# fpv-diversity.net
KiCad netlist of a schematic drawn in EAGLE
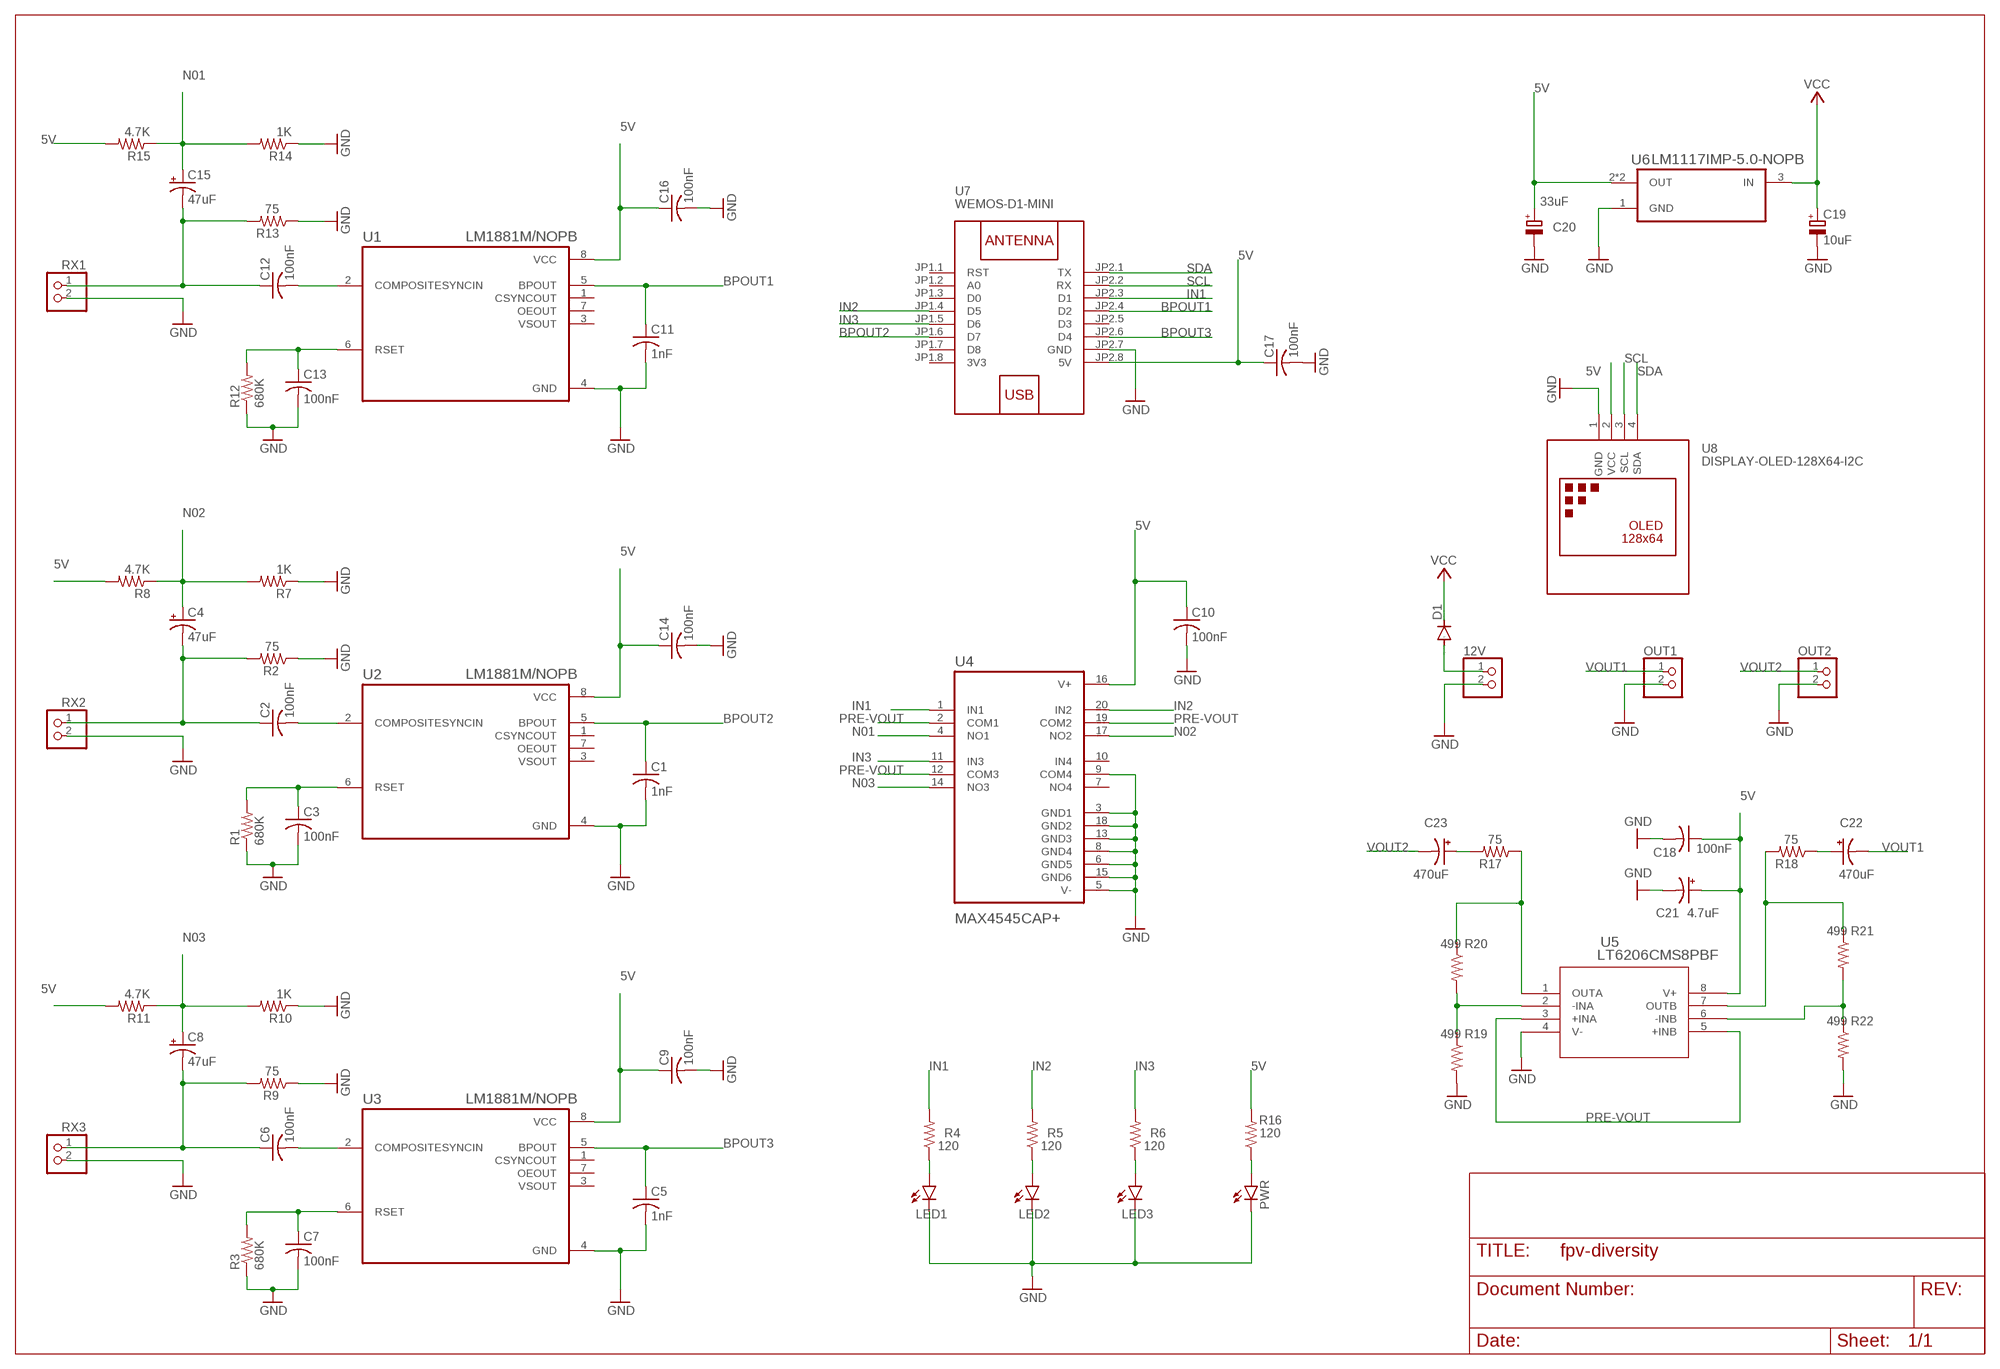
[diagram p0: schematic, sheet 1]

(export (version "E")
  (design (tool "Eeschema 10.0.6"))
  (components
    (comp (ref "12V")
      (value "PINHD-1X2")
      (footprint "eagle-import:1X02")
      (libsource (lib "eagle-import") (part "PINHD-1X2"))
    )
    (comp (ref "C1")
      (value "1nF")
      (footprint "eagle-import:C0603")
      (libsource (lib "eagle-import") (part "C-USC0603"))
    )
    (comp (ref "C2")
      (value "100nF")
      (footprint "eagle-import:C0805")
      (libsource (lib "eagle-import") (part "C-USC0805"))
    )
    (comp (ref "C3")
      (value "100nF")
      (footprint "eagle-import:C0805")
      (libsource (lib "eagle-import") (part "C-USC0805"))
    )
    (comp (ref "C4")
      (value "47uF")
      (footprint "eagle-import:CT3216")
      (libsource (lib "eagle-import") (part "CPOL-USCT3216"))
    )
    (comp (ref "C5")
      (value "1nF")
      (footprint "eagle-import:C0603")
      (libsource (lib "eagle-import") (part "C-USC0603"))
    )
    (comp (ref "C6")
      (value "100nF")
      (footprint "eagle-import:C0805")
      (libsource (lib "eagle-import") (part "C-USC0805"))
    )
    (comp (ref "C7")
      (value "100nF")
      (footprint "eagle-import:C0805")
      (libsource (lib "eagle-import") (part "C-USC0805"))
    )
    (comp (ref "C8")
      (value "47uF")
      (footprint "eagle-import:CT3216")
      (libsource (lib "eagle-import") (part "CPOL-USCT3216"))
    )
    (comp (ref "C9")
      (value "100nF")
      (footprint "eagle-import:C0805")
      (libsource (lib "eagle-import") (part "C-USC0805"))
    )
    (comp (ref "C10")
      (value "100nF")
      (footprint "eagle-import:C0805")
      (libsource (lib "eagle-import") (part "C-USC0805"))
    )
    (comp (ref "C11")
      (value "1nF")
      (footprint "eagle-import:C0603")
      (libsource (lib "eagle-import") (part "C-USC0603"))
    )
    (comp (ref "C12")
      (value "100nF")
      (footprint "eagle-import:C0805")
      (libsource (lib "eagle-import") (part "C-USC0805"))
    )
    (comp (ref "C13")
      (value "100nF")
      (footprint "eagle-import:C0805")
      (libsource (lib "eagle-import") (part "C-USC0805"))
    )
    (comp (ref "C14")
      (value "100nF")
      (footprint "eagle-import:C0805")
      (libsource (lib "eagle-import") (part "C-USC0805"))
    )
    (comp (ref "C15")
      (value "47uF")
      (footprint "eagle-import:CT3216")
      (libsource (lib "eagle-import") (part "CPOL-USCT3216"))
    )
    (comp (ref "C16")
      (value "100nF")
      (footprint "eagle-import:C0805")
      (libsource (lib "eagle-import") (part "C-USC0805"))
    )
    (comp (ref "C17")
      (value "100nF")
      (footprint "eagle-import:C0805")
      (libsource (lib "eagle-import") (part "C-USC0805"))
    )
    (comp (ref "C18")
      (value "100nF")
      (footprint "eagle-import:C0805")
      (libsource (lib "eagle-import") (part "C-USC0805"))
    )
    (comp (ref "C19")
      (value "10uF")
      (footprint "eagle-import:D_7343-31W")
      (libsource (lib "eagle-import") (part "CPOL-EUD/7343-31W"))
    )
    (comp (ref "C20")
      (value "33uF")
      (footprint "eagle-import:D_7343-31W")
      (libsource (lib "eagle-import") (part "CPOL-EUD/7343-31W"))
    )
    (comp (ref "C21")
      (value "4.7uF")
      (footprint "eagle-import:CT3528")
      (libsource (lib "eagle-import") (part "CPOL-USCT3528"))
    )
    (comp (ref "C22")
      (value "470uF")
      (footprint "eagle-import:UD-6,3X7,7_NICHICON")
      (libsource (lib "eagle-import") (part "CPOL-USUD-6,3X7,7"))
    )
    (comp (ref "C23")
      (value "470uF")
      (footprint "eagle-import:UD-6,3X7,7_NICHICON")
      (libsource (lib "eagle-import") (part "CPOL-USUD-6,3X7,7"))
    )
    (comp (ref "D1")
      (value "DIODE-DO-214AC")
      (footprint "eagle-import:DO-214AC")
      (libsource (lib "eagle-import") (part "DIODE-DO-214AC"))
    )
    (comp (ref "LED1")
      (value "LEDCHIPLED_0603")
      (footprint "eagle-import:CHIPLED_0603")
      (libsource (lib "eagle-import") (part "LEDCHIPLED_0603"))
    )
    (comp (ref "LED2")
      (value "LEDCHIPLED_0603")
      (footprint "eagle-import:CHIPLED_0603")
      (libsource (lib "eagle-import") (part "LEDCHIPLED_0603"))
    )
    (comp (ref "LED3")
      (value "LEDCHIPLED_0603")
      (footprint "eagle-import:CHIPLED_0603")
      (libsource (lib "eagle-import") (part "LEDCHIPLED_0603"))
    )
    (comp (ref "OUT1")
      (value "PINHD-1X2")
      (footprint "eagle-import:1X02")
      (libsource (lib "eagle-import") (part "PINHD-1X2"))
    )
    (comp (ref "OUT2")
      (value "PINHD-1X2")
      (footprint "eagle-import:1X02")
      (libsource (lib "eagle-import") (part "PINHD-1X2"))
    )
    (comp (ref "PWR")
      (value "LEDCHIPLED_0603")
      (footprint "eagle-import:CHIPLED_0603")
      (libsource (lib "eagle-import") (part "LEDCHIPLED_0603"))
    )
    (comp (ref "R1")
      (value "680K")
      (footprint "eagle-import:R0805")
      (libsource (lib "eagle-import") (part "R-US_R0805"))
    )
    (comp (ref "R2")
      (value "75")
      (footprint "eagle-import:R0805")
      (libsource (lib "eagle-import") (part "R-US_R0805"))
    )
    (comp (ref "R3")
      (value "680K")
      (footprint "eagle-import:R0805")
      (libsource (lib "eagle-import") (part "R-US_R0805"))
    )
    (comp (ref "R4")
      (value "120")
      (footprint "eagle-import:R0603")
      (libsource (lib "eagle-import") (part "R-US_R0603"))
    )
    (comp (ref "R5")
      (value "120")
      (footprint "eagle-import:R0603")
      (libsource (lib "eagle-import") (part "R-US_R0603"))
    )
    (comp (ref "R6")
      (value "120")
      (footprint "eagle-import:R0603")
      (libsource (lib "eagle-import") (part "R-US_R0603"))
    )
    (comp (ref "R7")
      (value "1K")
      (footprint "eagle-import:R0805")
      (libsource (lib "eagle-import") (part "R-US_R0805"))
    )
    (comp (ref "R8")
      (value "4.7K")
      (footprint "eagle-import:R0805")
      (libsource (lib "eagle-import") (part "R-US_R0805"))
    )
    (comp (ref "R9")
      (value "75")
      (footprint "eagle-import:R0805")
      (libsource (lib "eagle-import") (part "R-US_R0805"))
    )
    (comp (ref "R10")
      (value "1K")
      (footprint "eagle-import:R0805")
      (libsource (lib "eagle-import") (part "R-US_R0805"))
    )
    (comp (ref "R11")
      (value "4.7K")
      (footprint "eagle-import:R0805")
      (libsource (lib "eagle-import") (part "R-US_R0805"))
    )
    (comp (ref "R12")
      (value "680K")
      (footprint "eagle-import:R0805")
      (libsource (lib "eagle-import") (part "R-US_R0805"))
    )
    (comp (ref "R13")
      (value "75")
      (footprint "eagle-import:R0805")
      (libsource (lib "eagle-import") (part "R-US_R0805"))
    )
    (comp (ref "R14")
      (value "1K")
      (footprint "eagle-import:R0805")
      (libsource (lib "eagle-import") (part "R-US_R0805"))
    )
    (comp (ref "R15")
      (value "4.7K")
      (footprint "eagle-import:R0805")
      (libsource (lib "eagle-import") (part "R-US_R0805"))
    )
    (comp (ref "R16")
      (value "120")
      (footprint "eagle-import:R0603")
      (libsource (lib "eagle-import") (part "R-US_R0603"))
    )
    (comp (ref "R17")
      (value "75")
      (footprint "eagle-import:R0805")
      (libsource (lib "eagle-import") (part "R-US_R0805"))
    )
    (comp (ref "R18")
      (value "75")
      (footprint "eagle-import:R0805")
      (libsource (lib "eagle-import") (part "R-US_R0805"))
    )
    (comp (ref "R19")
      (value "499")
      (footprint "eagle-import:R1206")
      (libsource (lib "eagle-import") (part "R-US_R1206"))
    )
    (comp (ref "R20")
      (value "499")
      (footprint "eagle-import:R1206")
      (libsource (lib "eagle-import") (part "R-US_R1206"))
    )
    (comp (ref "R21")
      (value "499")
      (footprint "eagle-import:R1206")
      (libsource (lib "eagle-import") (part "R-US_R1206"))
    )
    (comp (ref "R22")
      (value "499")
      (footprint "eagle-import:R1206")
      (libsource (lib "eagle-import") (part "R-US_R1206"))
    )
    (comp (ref "RX1")
      (value "PINHD-1X2")
      (footprint "eagle-import:1X02")
      (libsource (lib "eagle-import") (part "PINHD-1X2"))
    )
    (comp (ref "RX2")
      (value "PINHD-1X2")
      (footprint "eagle-import:1X02")
      (libsource (lib "eagle-import") (part "PINHD-1X2"))
    )
    (comp (ref "RX3")
      (value "PINHD-1X2")
      (footprint "eagle-import:1X02")
      (libsource (lib "eagle-import") (part "PINHD-1X2"))
    )
    (comp (ref "U1")
      (value "LM1881M/NOPB")
      (footprint "eagle-import:SOIC127P599X175-8N")
      (fields (field (name "MF") "Texas Instruments"))
      (libsource (lib "eagle-import") (part "LM1881M/NOPB"))
    )
    (comp (ref "U2")
      (value "LM1881M/NOPB")
      (footprint "eagle-import:SOIC127P599X175-8N")
      (fields (field (name "MF") "Texas Instruments"))
      (libsource (lib "eagle-import") (part "LM1881M/NOPB"))
    )
    (comp (ref "U3")
      (value "LM1881M/NOPB")
      (footprint "eagle-import:SOIC127P599X175-8N")
      (fields (field (name "MF") "Texas Instruments"))
      (libsource (lib "eagle-import") (part "LM1881M/NOPB"))
    )
    (comp (ref "U4")
      (value "MAX4545CAP+")
      (footprint "eagle-import:SOP65P777X199-20N")
      (fields (field (name "MF") "Maxim Integrated"))
      (libsource (lib "eagle-import") (part "MAX4545CAP+"))
    )
    (comp (ref "U5")
      (value "LT6206CMS8PBF")
      (footprint "eagle-import:MSOP-8_MS")
      (fields (field (name "MF") "Analog Devices") (field (name "MP") "LT6206CMS8#PBF"))
      (libsource (lib "eagle-import") (part "LT6206CMS8PBF"))
    )
    (comp (ref "U6")
      (value "LM1117IMP-5.0-NOPB")
      (footprint "eagle-import:SOT230P700X180-4N")
      (fields (field (name "MF") "Texas Instruments") (field (name "MP") "LM1117IMP-5.0/NOPB"))
      (libsource (lib "eagle-import") (part "LM1117IMP-5.0-NOPB"))
    )
    (comp (ref "U7")
      (value "WEMOS-D1-MINI")
      (footprint "eagle-import:WEMOS-D1-MINI")
      (libsource (lib "eagle-import") (part "WEMOS-D1-MINI"))
    )
    (comp (ref "U8")
      (value "DISPLAY-OLED-128X64-I2C")
      (footprint "eagle-import:DISPLAY-OLED-128X64-I2C")
      (libsource (lib "eagle-import") (part "DISPLAY-OLED-128X64-I2C"))
    )
  )
  (nets
    (net (code "1") (name "/3V3") (class "Default")
      (node (ref "U7") (pin "JP1.8") (pinfunction "3V3_JP1.8") (pintype "power_in"))
    )
    (net (code "2") (name "/5V") (class "Default")
      (node (ref "C10") (pin "1") (pinfunction "1_1") (pintype "passive"))
      (node (ref "C14") (pin "1") (pinfunction "1_1") (pintype "passive"))
      (node (ref "C16") (pin "1") (pinfunction "1_1") (pintype "passive"))
      (node (ref "C17") (pin "1") (pinfunction "1_1") (pintype "passive"))
      (node (ref "C18") (pin "1") (pinfunction "1_1") (pintype "passive"))
      (node (ref "C20") (pin "+") (pinfunction "+_+") (pintype "passive"))
      (node (ref "C21") (pin "+") (pinfunction "+_+") (pintype "passive"))
      (node (ref "C9") (pin "1") (pinfunction "1_1") (pintype "passive"))
      (node (ref "R11") (pin "2") (pinfunction "2_2") (pintype "passive"))
      (node (ref "R15") (pin "2") (pinfunction "2_2") (pintype "passive"))
      (node (ref "R16") (pin "2") (pinfunction "2_2") (pintype "passive"))
      (node (ref "R8") (pin "2") (pinfunction "2_2") (pintype "passive"))
      (node (ref "U1") (pin "8") (pinfunction "VCC_8") (pintype "power_in"))
      (node (ref "U2") (pin "8") (pinfunction "VCC_8") (pintype "power_in"))
      (node (ref "U3") (pin "8") (pinfunction "VCC_8") (pintype "power_in"))
      (node (ref "U4") (pin "16") (pinfunction "V+_16") (pintype "power_in"))
      (node (ref "U5") (pin "8") (pinfunction "V+_8") (pintype "power_in"))
      (node (ref "U6") (pin "2") (pinfunction "OUT_2") (pintype "output"))
      (node (ref "U6") (pin "4") (pinfunction "OUT_4") (pintype "output"))
      (node (ref "U7") (pin "JP2.8") (pinfunction "5V_JP2.8") (pintype "power_in"))
      (node (ref "U8") (pin "2") (pinfunction "VCC_2") (pintype "power_in"))
    )
    (net (code "3") (name "/BPOUT1") (class "Default")
      (node (ref "C11") (pin "1") (pinfunction "1_1") (pintype "passive"))
      (node (ref "U1") (pin "5") (pinfunction "BPOUT_5") (pintype "output"))
      (node (ref "U7") (pin "JP2.4") (pinfunction "D2_JP2.4") (pintype "bidirectional"))
    )
    (net (code "4") (name "/BPOUT2") (class "Default")
      (node (ref "C1") (pin "1") (pinfunction "1_1") (pintype "passive"))
      (node (ref "U2") (pin "5") (pinfunction "BPOUT_5") (pintype "output"))
      (node (ref "U7") (pin "JP1.6") (pinfunction "D7_JP1.6") (pintype "bidirectional"))
    )
    (net (code "5") (name "/BPOUT3") (class "Default")
      (node (ref "C5") (pin "1") (pinfunction "1_1") (pintype "passive"))
      (node (ref "U3") (pin "5") (pinfunction "BPOUT_5") (pintype "output"))
      (node (ref "U7") (pin "JP2.6") (pinfunction "D4_JP2.6") (pintype "bidirectional"))
    )
    (net (code "6") (name "/IN1") (class "Default")
      (node (ref "R4") (pin "2") (pinfunction "2_2") (pintype "passive"))
      (node (ref "U4") (pin "1") (pinfunction "IN1_1") (pintype "input"))
      (node (ref "U7") (pin "JP2.3") (pinfunction "D1_JP2.3") (pintype "bidirectional"))
    )
    (net (code "7") (name "/IN2") (class "Default")
      (node (ref "R5") (pin "2") (pinfunction "2_2") (pintype "passive"))
      (node (ref "U4") (pin "20") (pinfunction "IN2_20") (pintype "input"))
      (node (ref "U7") (pin "JP1.4") (pinfunction "D5_JP1.4") (pintype "bidirectional"))
    )
    (net (code "8") (name "/IN3") (class "Default")
      (node (ref "R6") (pin "2") (pinfunction "2_2") (pintype "passive"))
      (node (ref "U4") (pin "11") (pinfunction "IN3_11") (pintype "input"))
      (node (ref "U7") (pin "JP1.5") (pinfunction "D6_JP1.5") (pintype "bidirectional"))
    )
    (net (code "9") (name "/N01") (class "Default")
      (node (ref "C15") (pin "+") (pinfunction "+_+") (pintype "passive"))
      (node (ref "R14") (pin "2") (pinfunction "2_2") (pintype "passive"))
      (node (ref "R15") (pin "1") (pinfunction "1_1") (pintype "passive"))
      (node (ref "U4") (pin "4") (pinfunction "NO1_4") (pintype "bidirectional"))
    )
    (net (code "10") (name "/N02") (class "Default")
      (node (ref "C4") (pin "+") (pinfunction "+_+") (pintype "passive"))
      (node (ref "R7") (pin "2") (pinfunction "2_2") (pintype "passive"))
      (node (ref "R8") (pin "1") (pinfunction "1_1") (pintype "passive"))
      (node (ref "U4") (pin "17") (pinfunction "NO2_17") (pintype "bidirectional"))
    )
    (net (code "11") (name "/N03") (class "Default")
      (node (ref "C8") (pin "+") (pinfunction "+_+") (pintype "passive"))
      (node (ref "R10") (pin "2") (pinfunction "2_2") (pintype "passive"))
      (node (ref "R11") (pin "1") (pinfunction "1_1") (pintype "passive"))
      (node (ref "U4") (pin "14") (pinfunction "NO3_14") (pintype "bidirectional"))
    )
    (net (code "12") (name "/PRE-VOUT") (class "Default")
      (node (ref "U4") (pin "12") (pinfunction "COM3_12") (pintype "bidirectional"))
      (node (ref "U4") (pin "19") (pinfunction "COM2_19") (pintype "bidirectional"))
      (node (ref "U4") (pin "2") (pinfunction "COM1_2") (pintype "bidirectional"))
      (node (ref "U5") (pin "3") (pinfunction "+INA_3") (pintype "input"))
      (node (ref "U5") (pin "5") (pinfunction "+INB_5") (pintype "input"))
    )
    (net (code "13") (name "/SCL") (class "Default")
      (node (ref "U7") (pin "JP2.2") (pinfunction "RX_JP2.2") (pintype "bidirectional"))
      (node (ref "U8") (pin "3") (pinfunction "SCL_3") (pintype "bidirectional"))
    )
    (net (code "14") (name "/SDA") (class "Default")
      (node (ref "U7") (pin "JP2.1") (pinfunction "TX_JP2.1") (pintype "bidirectional"))
      (node (ref "U8") (pin "4") (pinfunction "SDA_4") (pintype "bidirectional"))
    )
    (net (code "15") (name "/VOUT1") (class "Default")
      (node (ref "C22") (pin "-") (pinfunction "-_-") (pintype "passive"))
      (node (ref "OUT1") (pin "1") (pinfunction "1_1") (pintype "passive"))
    )
    (net (code "16") (name "/VOUT2") (class "Default")
      (node (ref "C23") (pin "-") (pinfunction "-_-") (pintype "passive"))
      (node (ref "OUT2") (pin "1") (pinfunction "1_1") (pintype "passive"))
    )
    (net (code "17") (name "GND") (class "Default")
      (node (ref "12V") (pin "2") (pinfunction "2_2") (pintype "passive"))
      (node (ref "C1") (pin "2") (pinfunction "2_2") (pintype "passive"))
      (node (ref "C10") (pin "2") (pinfunction "2_2") (pintype "passive"))
      (node (ref "C11") (pin "2") (pinfunction "2_2") (pintype "passive"))
      (node (ref "C13") (pin "2") (pinfunction "2_2") (pintype "passive"))
      (node (ref "C14") (pin "2") (pinfunction "2_2") (pintype "passive"))
      (node (ref "C16") (pin "2") (pinfunction "2_2") (pintype "passive"))
      (node (ref "C17") (pin "2") (pinfunction "2_2") (pintype "passive"))
      (node (ref "C18") (pin "2") (pinfunction "2_2") (pintype "passive"))
      (node (ref "C19") (pin "-") (pinfunction "-_-") (pintype "passive"))
      (node (ref "C20") (pin "-") (pinfunction "-_-") (pintype "passive"))
      (node (ref "C21") (pin "-") (pinfunction "-_-") (pintype "passive"))
      (node (ref "C3") (pin "2") (pinfunction "2_2") (pintype "passive"))
      (node (ref "C5") (pin "2") (pinfunction "2_2") (pintype "passive"))
      (node (ref "C7") (pin "2") (pinfunction "2_2") (pintype "passive"))
      (node (ref "C9") (pin "2") (pinfunction "2_2") (pintype "passive"))
      (node (ref "LED1") (pin "C") (pinfunction "C_C") (pintype "passive"))
      (node (ref "LED2") (pin "C") (pinfunction "C_C") (pintype "passive"))
      (node (ref "LED3") (pin "C") (pinfunction "C_C") (pintype "passive"))
      (node (ref "OUT1") (pin "2") (pinfunction "2_2") (pintype "passive"))
      (node (ref "OUT2") (pin "2") (pinfunction "2_2") (pintype "passive"))
      (node (ref "PWR") (pin "C") (pinfunction "C_C") (pintype "passive"))
      (node (ref "R1") (pin "1") (pinfunction "1_1") (pintype "passive"))
      (node (ref "R10") (pin "1") (pinfunction "1_1") (pintype "passive"))
      (node (ref "R12") (pin "1") (pinfunction "1_1") (pintype "passive"))
      (node (ref "R13") (pin "1") (pinfunction "1_1") (pintype "passive"))
      (node (ref "R14") (pin "1") (pinfunction "1_1") (pintype "passive"))
      (node (ref "R19") (pin "2") (pinfunction "2_2") (pintype "passive"))
      (node (ref "R2") (pin "1") (pinfunction "1_1") (pintype "passive"))
      (node (ref "R22") (pin "2") (pinfunction "2_2") (pintype "passive"))
      (node (ref "R3") (pin "1") (pinfunction "1_1") (pintype "passive"))
      (node (ref "R7") (pin "1") (pinfunction "1_1") (pintype "passive"))
      (node (ref "R9") (pin "1") (pinfunction "1_1") (pintype "passive"))
      (node (ref "RX1") (pin "2") (pinfunction "2_2") (pintype "passive"))
      (node (ref "RX2") (pin "2") (pinfunction "2_2") (pintype "passive"))
      (node (ref "RX3") (pin "2") (pinfunction "2_2") (pintype "passive"))
      (node (ref "U1") (pin "4") (pinfunction "GND_4") (pintype "power_in"))
      (node (ref "U2") (pin "4") (pinfunction "GND_4") (pintype "power_in"))
      (node (ref "U3") (pin "4") (pinfunction "GND_4") (pintype "power_in"))
      (node (ref "U4") (pin "13") (pinfunction "GND3_13") (pintype "power_in"))
      (node (ref "U4") (pin "15") (pinfunction "GND6_15") (pintype "power_in"))
      (node (ref "U4") (pin "18") (pinfunction "GND2_18") (pintype "power_in"))
      (node (ref "U4") (pin "3") (pinfunction "GND1_3") (pintype "power_in"))
      (node (ref "U4") (pin "5") (pinfunction "V-_5") (pintype "power_in"))
      (node (ref "U4") (pin "6") (pinfunction "GND5_6") (pintype "power_in"))
      (node (ref "U4") (pin "8") (pinfunction "GND4_8") (pintype "power_in"))
      (node (ref "U4") (pin "9") (pinfunction "COM4_9") (pintype "bidirectional"))
      (node (ref "U5") (pin "4") (pinfunction "V-_4") (pintype "power_in"))
      (node (ref "U6") (pin "1") (pinfunction "GND_1") (pintype "power_in"))
      (node (ref "U7") (pin "JP2.7") (pinfunction "GND_JP2.7") (pintype "power_in"))
      (node (ref "U8") (pin "1") (pinfunction "GND_1") (pintype "power_in"))
    )
    (net (code "18") (name "Net-(12V-Pad1)") (class "Default")
      (node (ref "12V") (pin "1") (pinfunction "1_1") (pintype "passive"))
      (node (ref "D1") (pin "A") (pinfunction "A_A") (pintype "passive"))
    )
    (net (code "19") (name "Net-(C2-Pad1)") (class "Default")
      (node (ref "C2") (pin "1") (pinfunction "1_1") (pintype "passive"))
      (node (ref "C4") (pin "-") (pinfunction "-_-") (pintype "passive"))
      (node (ref "R2") (pin "2") (pinfunction "2_2") (pintype "passive"))
      (node (ref "RX2") (pin "1") (pinfunction "1_1") (pintype "passive"))
    )
    (net (code "20") (name "Net-(C6-Pad1)") (class "Default")
      (node (ref "C6") (pin "1") (pinfunction "1_1") (pintype "passive"))
      (node (ref "C8") (pin "-") (pinfunction "-_-") (pintype "passive"))
      (node (ref "R9") (pin "2") (pinfunction "2_2") (pintype "passive"))
      (node (ref "RX3") (pin "1") (pinfunction "1_1") (pintype "passive"))
    )
    (net (code "21") (name "Net-(C12-Pad1)") (class "Default")
      (node (ref "C12") (pin "1") (pinfunction "1_1") (pintype "passive"))
      (node (ref "C15") (pin "-") (pinfunction "-_-") (pintype "passive"))
      (node (ref "R13") (pin "2") (pinfunction "2_2") (pintype "passive"))
      (node (ref "RX1") (pin "1") (pinfunction "1_1") (pintype "passive"))
    )
    (net (code "22") (name "Net-(C22-Pad+)") (class "Default")
      (node (ref "C22") (pin "+") (pinfunction "+_+") (pintype "passive"))
      (node (ref "R18") (pin "1") (pinfunction "1_1") (pintype "passive"))
    )
    (net (code "23") (name "Net-(C23-Pad+)") (class "Default")
      (node (ref "C23") (pin "+") (pinfunction "+_+") (pintype "passive"))
      (node (ref "R17") (pin "2") (pinfunction "2_2") (pintype "passive"))
    )
    (net (code "24") (name "Net-(LED1-PadA)") (class "Default")
      (node (ref "LED1") (pin "A") (pinfunction "A_A") (pintype "passive"))
      (node (ref "R4") (pin "1") (pinfunction "1_1") (pintype "passive"))
    )
    (net (code "25") (name "Net-(LED2-PadA)") (class "Default")
      (node (ref "LED2") (pin "A") (pinfunction "A_A") (pintype "passive"))
      (node (ref "R5") (pin "1") (pinfunction "1_1") (pintype "passive"))
    )
    (net (code "26") (name "Net-(LED3-PadA)") (class "Default")
      (node (ref "LED3") (pin "A") (pinfunction "A_A") (pintype "passive"))
      (node (ref "R6") (pin "1") (pinfunction "1_1") (pintype "passive"))
    )
    (net (code "27") (name "Net-(PWR-PadA)") (class "Default")
      (node (ref "PWR") (pin "A") (pinfunction "A_A") (pintype "passive"))
      (node (ref "R16") (pin "1") (pinfunction "1_1") (pintype "passive"))
    )
    (net (code "28") (name "Net-(U1-COMPOSITESYNCIN)") (class "Default")
      (node (ref "C12") (pin "2") (pinfunction "2_2") (pintype "passive"))
      (node (ref "U1") (pin "2") (pinfunction "COMPOSITESYNCIN_2") (pintype "input"))
    )
    (net (code "29") (name "Net-(U1-RSET)") (class "Default")
      (node (ref "C13") (pin "1") (pinfunction "1_1") (pintype "passive"))
      (node (ref "R12") (pin "2") (pinfunction "2_2") (pintype "passive"))
      (node (ref "U1") (pin "6") (pinfunction "RSET_6") (pintype "bidirectional"))
    )
    (net (code "30") (name "Net-(U2-COMPOSITESYNCIN)") (class "Default")
      (node (ref "C2") (pin "2") (pinfunction "2_2") (pintype "passive"))
      (node (ref "U2") (pin "2") (pinfunction "COMPOSITESYNCIN_2") (pintype "input"))
    )
    (net (code "31") (name "Net-(U2-RSET)") (class "Default")
      (node (ref "C3") (pin "1") (pinfunction "1_1") (pintype "passive"))
      (node (ref "R1") (pin "2") (pinfunction "2_2") (pintype "passive"))
      (node (ref "U2") (pin "6") (pinfunction "RSET_6") (pintype "bidirectional"))
    )
    (net (code "32") (name "Net-(U3-COMPOSITESYNCIN)") (class "Default")
      (node (ref "C6") (pin "2") (pinfunction "2_2") (pintype "passive"))
      (node (ref "U3") (pin "2") (pinfunction "COMPOSITESYNCIN_2") (pintype "input"))
    )
    (net (code "33") (name "Net-(U3-RSET)") (class "Default")
      (node (ref "C7") (pin "1") (pinfunction "1_1") (pintype "passive"))
      (node (ref "R3") (pin "2") (pinfunction "2_2") (pintype "passive"))
      (node (ref "U3") (pin "6") (pinfunction "RSET_6") (pintype "bidirectional"))
    )
    (net (code "34") (name "Net-(U5--INA)") (class "Default")
      (node (ref "R19") (pin "1") (pinfunction "1_1") (pintype "passive"))
      (node (ref "R20") (pin "2") (pinfunction "2_2") (pintype "passive"))
      (node (ref "U5") (pin "2") (pinfunction "-INA_2") (pintype "input"))
    )
    (net (code "35") (name "Net-(U5--INB)") (class "Default")
      (node (ref "R21") (pin "2") (pinfunction "2_2") (pintype "passive"))
      (node (ref "R22") (pin "1") (pinfunction "1_1") (pintype "passive"))
      (node (ref "U5") (pin "6") (pinfunction "-INB_6") (pintype "input"))
    )
    (net (code "36") (name "Net-(U5-OUTA)") (class "Default")
      (node (ref "R17") (pin "1") (pinfunction "1_1") (pintype "passive"))
      (node (ref "R20") (pin "1") (pinfunction "1_1") (pintype "passive"))
      (node (ref "U5") (pin "1") (pinfunction "OUTA_1") (pintype "output"))
    )
    (net (code "37") (name "Net-(U5-OUTB)") (class "Default")
      (node (ref "R18") (pin "2") (pinfunction "2_2") (pintype "passive"))
      (node (ref "R21") (pin "1") (pinfunction "1_1") (pintype "passive"))
      (node (ref "U5") (pin "7") (pinfunction "OUTB_7") (pintype "output"))
    )
    (net (code "38") (name "VCC") (class "Default")
      (node (ref "C19") (pin "+") (pinfunction "+_+") (pintype "passive"))
      (node (ref "D1") (pin "C") (pinfunction "C_C") (pintype "passive"))
      (node (ref "U6") (pin "3") (pinfunction "IN_3") (pintype "input"))
    )
    (net (code "39") (name "unconnected-(U1-CSYNCOUT-Pad1)") (class "Default")
      (node (ref "U1") (pin "1") (pinfunction "CSYNCOUT_1") (pintype "output"))
    )
    (net (code "40") (name "unconnected-(U1-OEOUT-Pad7)") (class "Default")
      (node (ref "U1") (pin "7") (pinfunction "OEOUT_7") (pintype "output"))
    )
    (net (code "41") (name "unconnected-(U1-VSOUT-Pad3)") (class "Default")
      (node (ref "U1") (pin "3") (pinfunction "VSOUT_3") (pintype "output"))
    )
    (net (code "42") (name "unconnected-(U2-CSYNCOUT-Pad1)") (class "Default")
      (node (ref "U2") (pin "1") (pinfunction "CSYNCOUT_1") (pintype "output"))
    )
    (net (code "43") (name "unconnected-(U2-OEOUT-Pad7)") (class "Default")
      (node (ref "U2") (pin "7") (pinfunction "OEOUT_7") (pintype "output"))
    )
    (net (code "44") (name "unconnected-(U2-VSOUT-Pad3)") (class "Default")
      (node (ref "U2") (pin "3") (pinfunction "VSOUT_3") (pintype "output"))
    )
    (net (code "45") (name "unconnected-(U3-CSYNCOUT-Pad1)") (class "Default")
      (node (ref "U3") (pin "1") (pinfunction "CSYNCOUT_1") (pintype "output"))
    )
    (net (code "46") (name "unconnected-(U3-OEOUT-Pad7)") (class "Default")
      (node (ref "U3") (pin "7") (pinfunction "OEOUT_7") (pintype "output"))
    )
    (net (code "47") (name "unconnected-(U3-VSOUT-Pad3)") (class "Default")
      (node (ref "U3") (pin "3") (pinfunction "VSOUT_3") (pintype "output"))
    )
    (net (code "48") (name "unconnected-(U4-IN4-Pad10)") (class "Default")
      (node (ref "U4") (pin "10") (pinfunction "IN4_10") (pintype "input"))
    )
    (net (code "49") (name "unconnected-(U4-NO4-Pad7)") (class "Default")
      (node (ref "U4") (pin "7") (pinfunction "NO4_7") (pintype "bidirectional"))
    )
    (net (code "50") (name "unconnected-(U7-A0-PadJP1.2)") (class "Default")
      (node (ref "U7") (pin "JP1.2") (pinfunction "A0_JP1.2") (pintype "bidirectional"))
    )
    (net (code "51") (name "unconnected-(U7-D0-PadJP1.3)") (class "Default")
      (node (ref "U7") (pin "JP1.3") (pinfunction "D0_JP1.3") (pintype "bidirectional"))
    )
    (net (code "52") (name "unconnected-(U7-D3-PadJP2.5)") (class "Default")
      (node (ref "U7") (pin "JP2.5") (pinfunction "D3_JP2.5") (pintype "bidirectional"))
    )
    (net (code "53") (name "unconnected-(U7-D8-PadJP1.7)") (class "Default")
      (node (ref "U7") (pin "JP1.7") (pinfunction "D8_JP1.7") (pintype "bidirectional"))
    )
    (net (code "54") (name "unconnected-(U7-RST-PadJP1.1)") (class "Default")
      (node (ref "U7") (pin "JP1.1") (pinfunction "RST_JP1.1") (pintype "bidirectional"))
    )
  )
)
